# 08-Power.net
KiCad netlist of a schematic drawn in Altium Designer
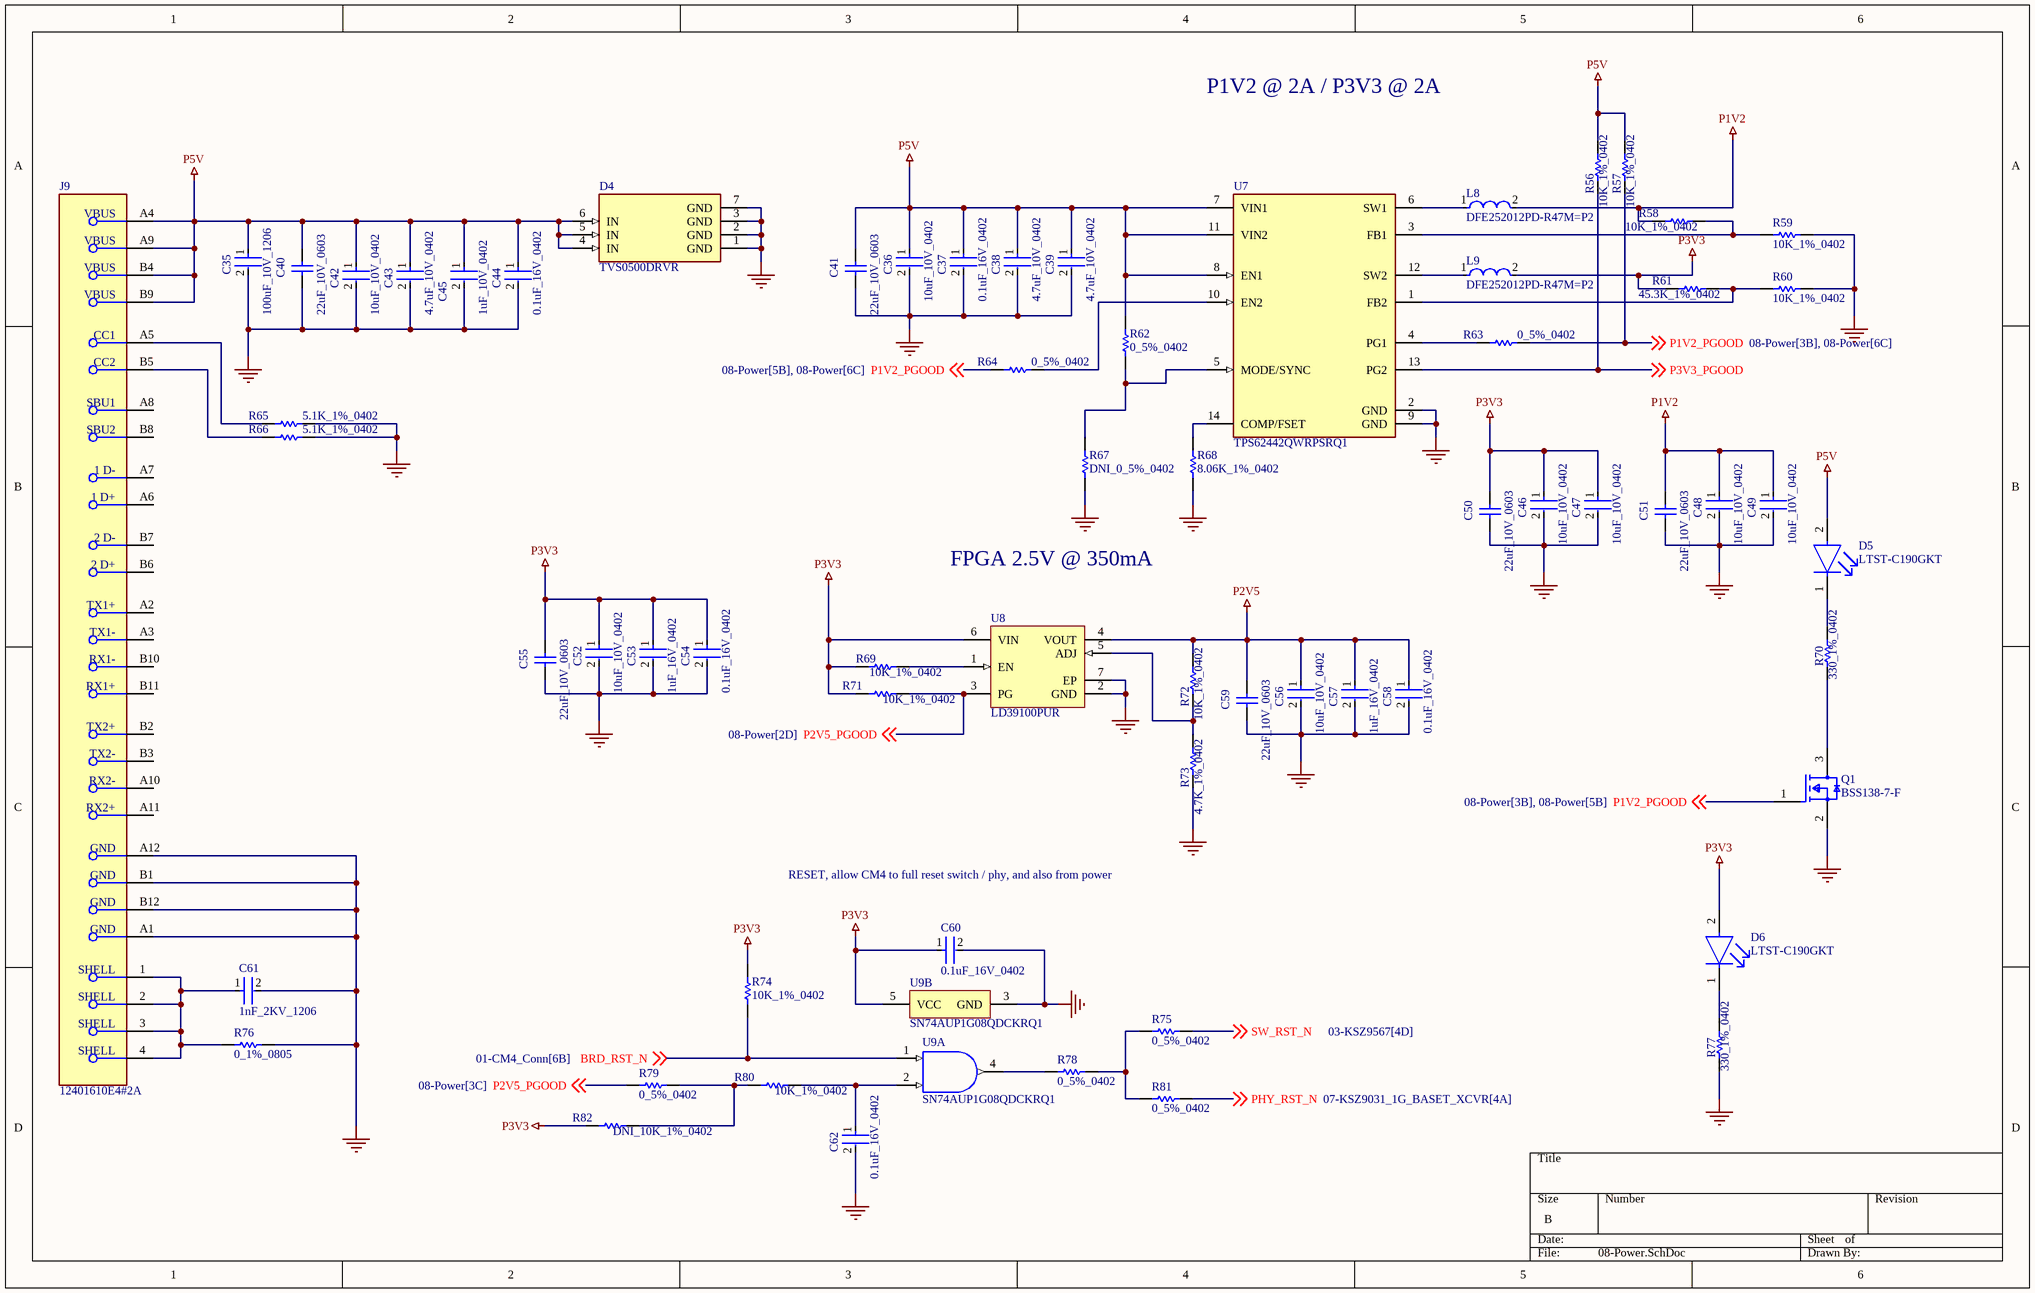
[diagram p0: 08-Power.SchDoc]

(export (version "E")
  (design (tool "Eeschema 10.0.6"))
  (components
    (comp (ref "C35")
      (value "100uF_10V_1206")
      (footprint "FP-C3216-160-0_3-IPC_C")
      (description "Multilayer Ceramic Capacitors 100uF ±20% 10V X5R SMD 1206")
      (fields (field (name "VOLTAGE") "10V") (field (name "TOLERANCE") "20%"))
      (libsource (lib "Altium Content Vault") (part "02cd4be3c70576c341d710602a673aa"))
    )
    (comp (ref "C36")
      (value "10uF_10V_0402")
      (footprint "FP-CL05A106MP5NUNC-MFG")
      (description "CAP CER 10UF 10V X5R 0402")
      (fields
        (field (name "OCTOPART") "https://octopart.com/cl05a106mp5nunc-samsung-22457395")
        (field (name "TOLERANCE") "20%")
      )
      (libsource (lib "Altium Content Vault") (part "b4654b650e69147ec39a6b967a45e02"))
    )
    (comp (ref "C37")
      (value "0.1uF_16V_0402")
      (footprint "FP-C0402-BB-MFG")
      (description "CAP CER 0.1UF 16V 5% X7R 0402")
      (fields
        (field (name "MANUFACTURER") "Kemet")
        (field (name "MANUFACTURER PART NUMBER") "C0402C104J4RACTU")
      )
      (libsource (lib "Altium Content Vault") (part "b4654b650e69147ec39a6b967a45e02"))
    )
    (comp (ref "C38")
      (value "4.7uF_10V_0402")
      (footprint "FP-C1005-050-0_15-MFG")
      (description "CAP CER 4.7UF 10V X5R 0402")
      (fields (field (name "TOLERANCE") "10%"))
      (libsource (lib "Altium Content Vault") (part "b4654b650e69147ec39a6b967a45e02"))
    )
    (comp (ref "C39")
      (value "4.7uF_10V_0402")
      (footprint "FP-C1005-050-0_15-MFG")
      (description "CAP CER 4.7UF 10V X5R 0402")
      (fields (field (name "TOLERANCE") "10%"))
      (libsource (lib "Altium Content Vault") (part "b4654b650e69147ec39a6b967a45e02"))
    )
    (comp (ref "C40")
      (value "22uF_10V_0603")
      (footprint "CAPC1608X100X20ML10")
      (description "Chip Capacitor, 22 uF, +/- 20%, 10 V, -55 to 85 degC, 0603 (1608 Metric), RoHS, Tape and Reel")
      (fields (field (name "MANUFACTURER") "TDK") (field (name "TOLERANCE") "±20%"))
      (libsource (lib "Altium Content Vault") (part "CAP-NP-2"))
    )
    (comp (ref "C41")
      (value "22uF_10V_0603")
      (footprint "CAPC1608X100X20ML10")
      (description "Chip Capacitor, 22 uF, +/- 20%, 10 V, -55 to 85 degC, 0603 (1608 Metric), RoHS, Tape and Reel")
      (fields (field (name "MANUFACTURER") "TDK") (field (name "TOLERANCE") "±20%"))
      (libsource (lib "Altium Content Vault") (part "CAP-NP-2"))
    )
    (comp (ref "C42")
      (value "10uF_10V_0402")
      (footprint "FP-CL05A106MP5NUNC-MFG")
      (description "CAP CER 10UF 10V X5R 0402")
      (fields
        (field (name "OCTOPART") "https://octopart.com/cl05a106mp5nunc-samsung-22457395")
        (field (name "TOLERANCE") "20%")
      )
      (libsource (lib "Altium Content Vault") (part "b4654b650e69147ec39a6b967a45e02"))
    )
    (comp (ref "C43")
      (value "4.7uF_10V_0402")
      (footprint "FP-C1005-050-0_15-MFG")
      (description "CAP CER 4.7UF 10V X5R 0402")
      (fields (field (name "TOLERANCE") "10%"))
      (libsource (lib "Altium Content Vault") (part "b4654b650e69147ec39a6b967a45e02"))
    )
    (comp (ref "C44")
      (value "0.1uF_16V_0402")
      (footprint "FP-C0402-BB-MFG")
      (description "CAP CER 0.1UF 16V 5% X7R 0402")
      (fields
        (field (name "MANUFACTURER") "Kemet")
        (field (name "MANUFACTURER PART NUMBER") "C0402C104J4RACTU")
      )
      (libsource (lib "Altium Content Vault") (part "b4654b650e69147ec39a6b967a45e02"))
    )
    (comp (ref "C45")
      (value "1uF_10V_0402")
      (footprint "FP-CL511-IPC_C")
      (description "Cap Ceramic 1uF 10V X5R ±10% SMD 0402 +85°C Paper T/R")
      (fields (field (name "TOLERANCE") "10%"))
      (libsource (lib "Altium Content Vault") (part "b4654b650e69147ec39a6b967a45e02"))
    )
    (comp (ref "C46")
      (value "10uF_10V_0402")
      (footprint "FP-CL05A106MP5NUNC-MFG")
      (description "CAP CER 10UF 10V X5R 0402")
      (fields
        (field (name "OCTOPART") "https://octopart.com/cl05a106mp5nunc-samsung-22457395")
        (field (name "TOLERANCE") "20%")
      )
      (libsource (lib "Altium Content Vault") (part "b4654b650e69147ec39a6b967a45e02"))
    )
    (comp (ref "C47")
      (value "10uF_10V_0402")
      (footprint "FP-CL05A106MP5NUNC-MFG")
      (description "CAP CER 10UF 10V X5R 0402")
      (fields
        (field (name "OCTOPART") "https://octopart.com/cl05a106mp5nunc-samsung-22457395")
        (field (name "TOLERANCE") "20%")
      )
      (libsource (lib "Altium Content Vault") (part "b4654b650e69147ec39a6b967a45e02"))
    )
    (comp (ref "C48")
      (value "10uF_10V_0402")
      (footprint "FP-CL05A106MP5NUNC-MFG")
      (description "CAP CER 10UF 10V X5R 0402")
      (fields
        (field (name "OCTOPART") "https://octopart.com/cl05a106mp5nunc-samsung-22457395")
        (field (name "TOLERANCE") "20%")
      )
      (libsource (lib "Altium Content Vault") (part "b4654b650e69147ec39a6b967a45e02"))
    )
    (comp (ref "C49")
      (value "10uF_10V_0402")
      (footprint "FP-CL05A106MP5NUNC-MFG")
      (description "CAP CER 10UF 10V X5R 0402")
      (fields
        (field (name "OCTOPART") "https://octopart.com/cl05a106mp5nunc-samsung-22457395")
        (field (name "TOLERANCE") "20%")
      )
      (libsource (lib "Altium Content Vault") (part "b4654b650e69147ec39a6b967a45e02"))
    )
    (comp (ref "C50")
      (value "22uF_10V_0603")
      (footprint "CAPC1608X100X20ML10")
      (description "Chip Capacitor, 22 uF, +/- 20%, 10 V, -55 to 85 degC, 0603 (1608 Metric), RoHS, Tape and Reel")
      (fields (field (name "MANUFACTURER") "TDK") (field (name "TOLERANCE") "±20%"))
      (libsource (lib "Altium Content Vault") (part "CAP-NP-2"))
    )
    (comp (ref "C51")
      (value "22uF_10V_0603")
      (footprint "CAPC1608X100X20ML10")
      (description "Chip Capacitor, 22 uF, +/- 20%, 10 V, -55 to 85 degC, 0603 (1608 Metric), RoHS, Tape and Reel")
      (fields (field (name "MANUFACTURER") "TDK") (field (name "TOLERANCE") "±20%"))
      (libsource (lib "Altium Content Vault") (part "CAP-NP-2"))
    )
    (comp (ref "C52")
      (value "10uF_10V_0402")
      (footprint "FP-CL05A106MP5NUNC-MFG")
      (description "CAP CER 10UF 10V X5R 0402")
      (fields
        (field (name "OCTOPART") "https://octopart.com/cl05a106mp5nunc-samsung-22457395")
        (field (name "TOLERANCE") "20%")
      )
      (libsource (lib "Altium Content Vault") (part "b4654b650e69147ec39a6b967a45e02"))
    )
    (comp (ref "C53")
      (value "1uF_16V_0402")
      (footprint "FP-0402-L_1_0_0_05-W_0_5-IPC_A")
      (description "None")
      (fields (field (name "TOLERANCE") "10%"))
      (libsource (lib "Altium Content Vault") (part "b4654b650e69147ec39a6b967a45e02"))
    )
    (comp (ref "C54")
      (value "0.1uF_16V_0402")
      (footprint "FP-C0402-BB-MFG")
      (description "CAP CER 0.1UF 16V 5% X7R 0402")
      (fields
        (field (name "MANUFACTURER") "Kemet")
        (field (name "MANUFACTURER PART NUMBER") "C0402C104J4RACTU")
      )
      (libsource (lib "Altium Content Vault") (part "b4654b650e69147ec39a6b967a45e02"))
    )
    (comp (ref "C55")
      (value "22uF_10V_0603")
      (footprint "CAPC1608X100X20ML10")
      (description "Chip Capacitor, 22 uF, +/- 20%, 10 V, -55 to 85 degC, 0603 (1608 Metric), RoHS, Tape and Reel")
      (fields (field (name "MANUFACTURER") "TDK") (field (name "TOLERANCE") "±20%"))
      (libsource (lib "Altium Content Vault") (part "CAP-NP-2"))
    )
    (comp (ref "C56")
      (value "10uF_10V_0402")
      (footprint "FP-CL05A106MP5NUNC-MFG")
      (description "CAP CER 10UF 10V X5R 0402")
      (fields
        (field (name "OCTOPART") "https://octopart.com/cl05a106mp5nunc-samsung-22457395")
        (field (name "TOLERANCE") "20%")
      )
      (libsource (lib "Altium Content Vault") (part "b4654b650e69147ec39a6b967a45e02"))
    )
    (comp (ref "C57")
      (value "1uF_16V_0402")
      (footprint "FP-0402-L_1_0_0_05-W_0_5-IPC_A")
      (description "None")
      (fields (field (name "TOLERANCE") "10%"))
      (libsource (lib "Altium Content Vault") (part "b4654b650e69147ec39a6b967a45e02"))
    )
    (comp (ref "C58")
      (value "0.1uF_16V_0402")
      (footprint "FP-C0402-BB-MFG")
      (description "CAP CER 0.1UF 16V 5% X7R 0402")
      (fields
        (field (name "MANUFACTURER") "Kemet")
        (field (name "MANUFACTURER PART NUMBER") "C0402C104J4RACTU")
      )
      (libsource (lib "Altium Content Vault") (part "b4654b650e69147ec39a6b967a45e02"))
    )
    (comp (ref "C59")
      (value "22uF_10V_0603")
      (footprint "CAPC1608X100X20ML10")
      (description "Chip Capacitor, 22 uF, +/- 20%, 10 V, -55 to 85 degC, 0603 (1608 Metric), RoHS, Tape and Reel")
      (fields (field (name "MANUFACTURER") "TDK") (field (name "TOLERANCE") "±20%"))
      (libsource (lib "Altium Content Vault") (part "CAP-NP-2"))
    )
    (comp (ref "C60")
      (value "0.1uF_16V_0402")
      (footprint "FP-C0402-BB-MFG")
      (description "CAP CER 0.1UF 16V 5% X7R 0402")
      (fields
        (field (name "MANUFACTURER") "Kemet")
        (field (name "MANUFACTURER PART NUMBER") "C0402C104J4RACTU")
      )
      (libsource (lib "Altium Content Vault") (part "b4654b650e69147ec39a6b967a45e02"))
    )
    (comp (ref "C61")
      (value "1nF_2KV_1206")
      (footprint "FP-CC1206-0_3-1_45-IPC_C")
      (description "CAP CER 1000PF 2KV X7R 1206")
      (fields (field (name "TOLERANCE") "10%") (field (name "VOLTAGE") "2kV"))
      (libsource (lib "Altium Content Vault") (part "02cd4be3c70576c341d710602a673aa"))
    )
    (comp (ref "C62")
      (value "0.1uF_16V_0402")
      (footprint "FP-C0402-BB-MFG")
      (description "CAP CER 0.1UF 16V 5% X7R 0402")
      (fields
        (field (name "MANUFACTURER") "Kemet")
        (field (name "MANUFACTURER PART NUMBER") "C0402C104J4RACTU")
      )
      (libsource (lib "Altium Content Vault") (part "b4654b650e69147ec39a6b967a45e02"))
    )
    (comp (ref "D4")
      (value "TVS0500DRVR")
      (footprint "FP-DRV0006A-MFG")
      (description "UNIDIR PRECISION SURGE DIODE")
      (libsource (lib "Altium Content Vault") (part "41370df9eefb4491f57eee86c9ac516"))
    )
    (comp (ref "D5")
      (value "LTST-C190GKT")
      (footprint "FP-LTST-C190GKT-MFG")
      (description "LED GREEN CLEAR CHIP SMD")
      (fields (field (name "VOLTAGE") "2V"))
      (libsource (lib "Altium Content Vault") (part "8706943c75ba83719d021d2fdc84c58"))
    )
    (comp (ref "D6")
      (value "LTST-C190GKT")
      (footprint "FP-LTST-C190GKT-MFG")
      (description "LED GREEN CLEAR CHIP SMD")
      (fields (field (name "VOLTAGE") "2V"))
      (libsource (lib "Altium Content Vault") (part "8706943c75ba83719d021d2fdc84c58"))
    )
    (comp (ref "J9")
      (value "12401610E4#2A")
      (footprint "FP-12401610E4#2A-MFG")
      (description "CONN RCP USB3.1 TYPEC 24P SMD RA")
      (libsource (lib "Altium Content Vault") (part "7c76f4c47d7e2af8b8797da79635f2a"))
    )
    (comp (ref "L8")
      (value "DFE252012PD-R47M=P2")
      (footprint "FP-DFE252012C-IPC_A")
      (description "Shielded Wirewound Inductor 0.47uH 20% 4000mA 0.027Ω 1008 (2520)")
      (libsource (lib "Altium Content Vault") (part "725321dda6339637d4d059423bc1c3c"))
    )
    (comp (ref "L9")
      (value "DFE252012PD-R47M=P2")
      (footprint "FP-DFE252012C-IPC_A")
      (description "Shielded Wirewound Inductor 0.47uH 20% 4000mA 0.027Ω 1008 (2520)")
      (libsource (lib "Altium Content Vault") (part "725321dda6339637d4d059423bc1c3c"))
    )
    (comp (ref "Q1")
      (value "BSS138-7-F")
      (footprint "FP-SOT23_Standard-MFG")
      (fields (field (name "VOLTAGE") "50V"))
      (libsource (lib "Altium Content Vault") (part "0a9ea7c96deaaede766a5b531c28de0"))
    )
    (comp (ref "R56")
      (value "10K_1%_0402")
      (footprint "RESC1005X40X25NL10T10")
      (fields (field (name "MANUFACTURER") "Bourns") (field (name "PART NUMBER") "CR0402-FX-1002GLF"))
      (libsource (lib "Altium Content Vault") (part "RES"))
    )
    (comp (ref "R57")
      (value "10K_1%_0402")
      (footprint "RESC1005X40X25NL10T10")
      (fields (field (name "MANUFACTURER") "Bourns") (field (name "PART NUMBER") "CR0402-FX-1002GLF"))
      (libsource (lib "Altium Content Vault") (part "RES"))
    )
    (comp (ref "R58")
      (value "10K_1%_0402")
      (footprint "RESC1005X40X25NL10T10")
      (fields (field (name "MANUFACTURER") "Bourns") (field (name "PART NUMBER") "CR0402-FX-1002GLF"))
      (libsource (lib "Altium Content Vault") (part "RES"))
    )
    (comp (ref "R59")
      (value "10K_1%_0402")
      (footprint "RESC1005X40X25NL10T10")
      (fields (field (name "MANUFACTURER") "Bourns") (field (name "PART NUMBER") "CR0402-FX-1002GLF"))
      (libsource (lib "Altium Content Vault") (part "RES"))
    )
    (comp (ref "R60")
      (value "10K_1%_0402")
      (footprint "RESC1005X40X25NL10T10")
      (fields (field (name "MANUFACTURER") "Bourns") (field (name "PART NUMBER") "CR0402-FX-1002GLF"))
      (libsource (lib "Altium Content Vault") (part "RES"))
    )
    (comp (ref "R61")
      (value "45.3K_1%_0402")
      (footprint "RESC0402(1005)_L")
      (description "45K3 0.063W 1% 0402 (1005 Metric)  SMD")
      (fields (field (name "TOLERANCE") "1 %") (field (name "POWER") "0.063 W"))
      (libsource (lib "Altium Content Vault") (part "RES"))
    )
    (comp (ref "R62")
      (value "0_5%_0402")
      (footprint "RESC1005X40X25NL05T10")
      (fields (field (name "MANUFACTURER") "Panasonic") (field (name "PART NUMBER") "ERJ-U020R00X"))
      (libsource (lib "Altium Content Vault") (part "RES"))
    )
    (comp (ref "R63")
      (value "0_5%_0402")
      (footprint "RESC1005X40X25NL05T10")
      (fields (field (name "MANUFACTURER") "Panasonic") (field (name "PART NUMBER") "ERJ-U020R00X"))
      (libsource (lib "Altium Content Vault") (part "RES"))
    )
    (comp (ref "R64")
      (value "0_5%_0402")
      (footprint "RESC1005X40X25NL05T10")
      (fields (field (name "MANUFACTURER") "Panasonic") (field (name "PART NUMBER") "ERJ-U020R00X"))
      (libsource (lib "Altium Content Vault") (part "RES"))
    )
    (comp (ref "R65")
      (value "5.1K_1%_0402")
      (footprint "RESC1005X40X25NL05T10")
      (fields (field (name "PART NUMBER") "RC0402FR-075K1L") (field (name "MANUFACTURER") "Yageo / Phycomp"))
      (libsource (lib "Altium Content Vault") (part "RES"))
    )
    (comp (ref "R66")
      (value "5.1K_1%_0402")
      (footprint "RESC1005X40X25NL05T10")
      (fields (field (name "PART NUMBER") "RC0402FR-075K1L") (field (name "MANUFACTURER") "Yageo / Phycomp"))
      (libsource (lib "Altium Content Vault") (part "RES"))
    )
    (comp (ref "R67")
      (value "DNI_0_5%_0402")
      (footprint "RESC1005X40X25NL05T10")
      (fields (field (name "MANUFACTURER") "Panasonic") (field (name "PART NUMBER") "ERJ-U020R00X"))
      (libsource (lib "Altium Content Vault") (part "RES"))
    )
    (comp (ref "R68")
      (value "8.06K_1%_0402")
      (footprint "RESC1005X40X25ML05T05")
      (description "Chip Resistor, 8.06 KOhm, +/- 1%, 63 mW, -55 to 155 degC, 0402 (1005 Metric), RoHS, Tape and Reel")
      (fields (field (name "PARTNUMBER") "CRCW04028K06FKED") (field (name "TOLERANCE") "1%"))
      (libsource (lib "Altium Content Vault") (part "RES-2"))
    )
    (comp (ref "R69")
      (value "10K_1%_0402")
      (footprint "RESC1005X40X25NL10T10")
      (fields (field (name "MANUFACTURER") "Bourns") (field (name "PART NUMBER") "CR0402-FX-1002GLF"))
      (libsource (lib "Altium Content Vault") (part "RES"))
    )
    (comp (ref "R70")
      (value "330_1%_0402")
      (footprint "RESC1005X40X25NL10T10")
      (fields (field (name "MANUFACTURER") "Panasonic") (field (name "PART NUMBER") "ERA-2AED331X"))
      (libsource (lib "Altium Content Vault") (part "RES"))
    )
    (comp (ref "R71")
      (value "10K_1%_0402")
      (footprint "RESC1005X40X25NL10T10")
      (fields (field (name "MANUFACTURER") "Bourns") (field (name "PART NUMBER") "CR0402-FX-1002GLF"))
      (libsource (lib "Altium Content Vault") (part "RES"))
    )
    (comp (ref "R72")
      (value "10K_1%_0402")
      (footprint "RESC1005X40X25NL10T10")
      (fields (field (name "MANUFACTURER") "Bourns") (field (name "PART NUMBER") "CR0402-FX-1002GLF"))
      (libsource (lib "Altium Content Vault") (part "RES"))
    )
    (comp (ref "R73")
      (value "4.7K_1%_0402")
      (footprint "RESC1005X40X25NL10T10")
      (fields (field (name "MANUFACTURER") "Bourns") (field (name "PART NUMBER") "CR0402-FX-4701GLF"))
      (libsource (lib "Altium Content Vault") (part "RES"))
    )
    (comp (ref "R74")
      (value "10K_1%_0402")
      (footprint "RESC1005X40X25NL10T10")
      (fields (field (name "MANUFACTURER") "Bourns") (field (name "PART NUMBER") "CR0402-FX-1002GLF"))
      (libsource (lib "Altium Content Vault") (part "RES"))
    )
    (comp (ref "R75")
      (value "0_5%_0402")
      (footprint "RESC1005X40X25NL05T10")
      (fields (field (name "MANUFACTURER") "Panasonic") (field (name "PART NUMBER") "ERJ-U020R00X"))
      (libsource (lib "Altium Content Vault") (part "RES"))
    )
    (comp (ref "R76")
      (value "0_1%_0805")
      (footprint "RESC2013X60X35NL10T20")
      (fields (field (name "MANUFACTURER") "Yageo") (field (name "PART NUMBER") "AC0805FR-070RL"))
      (libsource (lib "Altium Content Vault") (part "RES"))
    )
    (comp (ref "R77")
      (value "330_1%_0402")
      (footprint "RESC1005X40X25NL10T10")
      (fields (field (name "MANUFACTURER") "Panasonic") (field (name "PART NUMBER") "ERA-2AED331X"))
      (libsource (lib "Altium Content Vault") (part "RES"))
    )
    (comp (ref "R78")
      (value "0_5%_0402")
      (footprint "RESC1005X40X25NL05T10")
      (fields (field (name "MANUFACTURER") "Panasonic") (field (name "PART NUMBER") "ERJ-U020R00X"))
      (libsource (lib "Altium Content Vault") (part "RES"))
    )
    (comp (ref "R79")
      (value "0_5%_0402")
      (footprint "RESC1005X40X25NL05T10")
      (fields (field (name "MANUFACTURER") "Panasonic") (field (name "PART NUMBER") "ERJ-U020R00X"))
      (libsource (lib "Altium Content Vault") (part "RES"))
    )
    (comp (ref "R80")
      (value "10K_1%_0402")
      (footprint "RESC1005X40X25NL10T10")
      (fields (field (name "MANUFACTURER") "Bourns") (field (name "PART NUMBER") "CR0402-FX-1002GLF"))
      (libsource (lib "Altium Content Vault") (part "RES"))
    )
    (comp (ref "R81")
      (value "0_5%_0402")
      (footprint "RESC1005X40X25NL05T10")
      (fields (field (name "MANUFACTURER") "Panasonic") (field (name "PART NUMBER") "ERJ-U020R00X"))
      (libsource (lib "Altium Content Vault") (part "RES"))
    )
    (comp (ref "R82")
      (value "DNI_10K_1%_0402")
      (footprint "RESC1005X40X25NL10T10")
      (fields (field (name "MANUFACTURER") "Bourns") (field (name "PART NUMBER") "CR0402-FX-1002GLF"))
      (libsource (lib "Altium Content Vault") (part "RES"))
    )
    (comp (ref "U7")
      (value "TPS62442QWRPSRQ1")
      (footprint "FP-RQR0014A-MFG")
      (description "Adjustable-Frequency Dual Step-Down Converter, 2.7-6V VIN, 0.6-5.5V 2A VOUT, VQFN-HR14")
      (libsource (lib "Altium Content Vault") (part "72c5b9bb22caeb688b1070b758806aa"))
    )
    (comp (ref "U8")
      (value "LD39100PUR")
      (footprint "DFN6D_M")
      (libsource (lib "Altium Content Vault") (part "PM-REG-LD39050-SQ7A"))
    )
    (comp (ref "U9")
      (value "SN74AUP1G08QDCKRQ1")
      (footprint "DCK0005A_L")
      (description "Automotive Catalog Low-Power Single 2-Input Positive-AND Gate, DCK0005A, LARGE T&R")
      (fields
        (field (name "MANUFACTURER") "Texas Instruments")
        (field (name "GENERIC PART NUMBER") "SN74AUP1G08-Q1")
      )
      (libsource (lib "Altium Content Vault") (part "TI-SN74XXX1X08-5"))
    )
  )
  (nets
    (net (code "1") (name "BRD_RST_N") (class "Default")
      (node (ref "R74") (pin "2") (pinfunction "2_2") (pintype "passive"))
      (node (ref "U9") (pin "1") (pinfunction "A_1") (pintype "input"))
    )
    (net (code "2") (name "GND") (class "Default")
      (node (ref "C35") (pin "2") (pinfunction "2_2") (pintype "passive"))
      (node (ref "C36") (pin "2") (pinfunction "2_2") (pintype "passive"))
      (node (ref "C37") (pin "2") (pinfunction "2_2") (pintype "passive"))
      (node (ref "C38") (pin "2") (pinfunction "2_2") (pintype "passive"))
      (node (ref "C39") (pin "2") (pinfunction "2_2") (pintype "passive"))
      (node (ref "C40") (pin "1") (pinfunction "1_1") (pintype "passive"))
      (node (ref "C41") (pin "1") (pinfunction "1_1") (pintype "passive"))
      (node (ref "C42") (pin "2") (pinfunction "2_2") (pintype "passive"))
      (node (ref "C43") (pin "2") (pinfunction "2_2") (pintype "passive"))
      (node (ref "C44") (pin "2") (pinfunction "2_2") (pintype "passive"))
      (node (ref "C45") (pin "2") (pinfunction "2_2") (pintype "passive"))
      (node (ref "C46") (pin "2") (pinfunction "2_2") (pintype "passive"))
      (node (ref "C47") (pin "2") (pinfunction "2_2") (pintype "passive"))
      (node (ref "C48") (pin "2") (pinfunction "2_2") (pintype "passive"))
      (node (ref "C49") (pin "2") (pinfunction "2_2") (pintype "passive"))
      (node (ref "C50") (pin "1") (pinfunction "1_1") (pintype "passive"))
      (node (ref "C51") (pin "1") (pinfunction "1_1") (pintype "passive"))
      (node (ref "C52") (pin "2") (pinfunction "2_2") (pintype "passive"))
      (node (ref "C53") (pin "2") (pinfunction "2_2") (pintype "passive"))
      (node (ref "C54") (pin "2") (pinfunction "2_2") (pintype "passive"))
      (node (ref "C55") (pin "1") (pinfunction "1_1") (pintype "passive"))
      (node (ref "C56") (pin "2") (pinfunction "2_2") (pintype "passive"))
      (node (ref "C57") (pin "2") (pinfunction "2_2") (pintype "passive"))
      (node (ref "C58") (pin "2") (pinfunction "2_2") (pintype "passive"))
      (node (ref "C59") (pin "1") (pinfunction "1_1") (pintype "passive"))
      (node (ref "C60") (pin "2") (pinfunction "2_2") (pintype "passive"))
      (node (ref "C61") (pin "2") (pinfunction "2_2") (pintype "passive"))
      (node (ref "C62") (pin "2") (pinfunction "2_2") (pintype "passive"))
      (node (ref "D4") (pin "1") (pinfunction "GND_1") (pintype "power_in"))
      (node (ref "D4") (pin "2") (pinfunction "GND_2") (pintype "power_in"))
      (node (ref "D4") (pin "3") (pinfunction "GND_3") (pintype "power_in"))
      (node (ref "D4") (pin "7") (pinfunction "GND_7") (pintype "power_in"))
      (node (ref "J9") (pin "A1") (pinfunction "GND_A1") (pintype "power_in"))
      (node (ref "J9") (pin "A12") (pinfunction "GND_A12") (pintype "power_in"))
      (node (ref "J9") (pin "B1") (pinfunction "GND_B1") (pintype "power_in"))
      (node (ref "J9") (pin "B12") (pinfunction "GND_B12") (pintype "power_in"))
      (node (ref "Q1") (pin "2") (pinfunction "S_2") (pintype "passive"))
      (node (ref "R59") (pin "1") (pinfunction "1_1") (pintype "passive"))
      (node (ref "R60") (pin "1") (pinfunction "1_1") (pintype "passive"))
      (node (ref "R65") (pin "2") (pinfunction "2_2") (pintype "passive"))
      (node (ref "R66") (pin "2") (pinfunction "2_2") (pintype "passive"))
      (node (ref "R67") (pin "1") (pinfunction "1_1") (pintype "passive"))
      (node (ref "R68") (pin "1") (pinfunction "1_1") (pintype "passive"))
      (node (ref "R73") (pin "1") (pinfunction "1_1") (pintype "passive"))
      (node (ref "R76") (pin "2") (pinfunction "2_2") (pintype "passive"))
      (node (ref "R77") (pin "1") (pinfunction "1_1") (pintype "passive"))
      (node (ref "U7") (pin "2") (pinfunction "GND_2") (pintype "power_in"))
      (node (ref "U7") (pin "9") (pinfunction "GND_9") (pintype "power_in"))
      (node (ref "U8") (pin "2") (pinfunction "GND_2") (pintype "power_in"))
      (node (ref "U8") (pin "7") (pinfunction "EP_7") (pintype "power_in"))
      (node (ref "U9") (pin "3") (pinfunction "GND_3") (pintype "power_in"))
    )
    (net (code "3") (name "Net-(C61-Pad1)") (class "Default")
      (node (ref "C61") (pin "1") (pinfunction "1_1") (pintype "passive"))
      (node (ref "J9") (pin "1") (pinfunction "SHELL_1") (pintype "power_in"))
      (node (ref "J9") (pin "2") (pinfunction "SHELL_2") (pintype "power_in"))
      (node (ref "J9") (pin "3") (pinfunction "SHELL_3") (pintype "power_in"))
      (node (ref "J9") (pin "4") (pinfunction "SHELL_4") (pintype "power_in"))
      (node (ref "R76") (pin "1") (pinfunction "1_1") (pintype "passive"))
    )
    (net (code "4") (name "Net-(D5-C)") (class "Default")
      (node (ref "D5") (pin "1") (pinfunction "C_1") (pintype "passive"))
      (node (ref "R70") (pin "2") (pinfunction "2_2") (pintype "passive"))
    )
    (net (code "5") (name "Net-(D6-C)") (class "Default")
      (node (ref "D6") (pin "1") (pinfunction "C_1") (pintype "passive"))
      (node (ref "R77") (pin "2") (pinfunction "2_2") (pintype "passive"))
    )
    (net (code "6") (name "Net-(J9-CC1)") (class "Default")
      (node (ref "J9") (pin "A5") (pinfunction "CC1_A5") (pintype "passive"))
      (node (ref "R65") (pin "1") (pinfunction "1_1") (pintype "passive"))
    )
    (net (code "7") (name "Net-(J9-CC2)") (class "Default")
      (node (ref "J9") (pin "B5") (pinfunction "CC2_B5") (pintype "passive"))
      (node (ref "R66") (pin "1") (pinfunction "1_1") (pintype "passive"))
    )
    (net (code "8") (name "Net-(Q1-D)") (class "Default")
      (node (ref "Q1") (pin "3") (pinfunction "D_3") (pintype "passive"))
      (node (ref "R70") (pin "1") (pinfunction "1_1") (pintype "passive"))
    )
    (net (code "9") (name "Net-(R75-Pad2)") (class "Default")
      (node (ref "R75") (pin "2") (pinfunction "2_2") (pintype "passive"))
      (node (ref "R78") (pin "1") (pinfunction "1_1") (pintype "passive"))
      (node (ref "R81") (pin "2") (pinfunction "2_2") (pintype "passive"))
    )
    (net (code "10") (name "Net-(R79-Pad1)") (class "Default")
      (node (ref "R79") (pin "1") (pinfunction "1_1") (pintype "passive"))
      (node (ref "R80") (pin "2") (pinfunction "2_2") (pintype "passive"))
      (node (ref "R82") (pin "1") (pinfunction "1_1") (pintype "passive"))
    )
    (net (code "11") (name "Net-(U7-COMP{slash}FSET)") (class "Default")
      (node (ref "R68") (pin "2") (pinfunction "2_2") (pintype "passive"))
      (node (ref "U7") (pin "14") (pinfunction "COMP/FSET_14") (pintype "passive"))
    )
    (net (code "12") (name "Net-(U7-EN2)") (class "Default")
      (node (ref "R64") (pin "2") (pinfunction "2_2") (pintype "passive"))
      (node (ref "U7") (pin "10") (pinfunction "EN2_10") (pintype "input"))
    )
    (net (code "13") (name "Net-(U7-FB1)") (class "Default")
      (node (ref "R58") (pin "1") (pinfunction "1_1") (pintype "passive"))
      (node (ref "R59") (pin "2") (pinfunction "2_2") (pintype "passive"))
      (node (ref "U7") (pin "3") (pinfunction "FB1_3") (pintype "passive"))
    )
    (net (code "14") (name "Net-(U7-FB2)") (class "Default")
      (node (ref "R60") (pin "2") (pinfunction "2_2") (pintype "passive"))
      (node (ref "R61") (pin "2") (pinfunction "2_2") (pintype "passive"))
      (node (ref "U7") (pin "1") (pinfunction "FB2_1") (pintype "passive"))
    )
    (net (code "15") (name "Net-(U7-MODE{slash}SYNC)") (class "Default")
      (node (ref "R62") (pin "1") (pinfunction "1_1") (pintype "passive"))
      (node (ref "R67") (pin "2") (pinfunction "2_2") (pintype "passive"))
      (node (ref "U7") (pin "5") (pinfunction "MODE/SYNC_5") (pintype "input"))
    )
    (net (code "16") (name "Net-(U7-PG1)") (class "Default")
      (node (ref "R63") (pin "1") (pinfunction "1_1") (pintype "passive"))
      (node (ref "U7") (pin "4") (pinfunction "PG1_4") (pintype "open_collector"))
    )
    (net (code "17") (name "Net-(U7-SW1)") (class "Default")
      (node (ref "L8") (pin "1") (pinfunction "1_1") (pintype "passive"))
      (node (ref "U7") (pin "6") (pinfunction "SW1_6") (pintype "passive"))
    )
    (net (code "18") (name "Net-(U7-SW2)") (class "Default")
      (node (ref "L9") (pin "1") (pinfunction "1_1") (pintype "passive"))
      (node (ref "U7") (pin "12") (pinfunction "SW2_12") (pintype "passive"))
    )
    (net (code "19") (name "Net-(U8-ADJ)") (class "Default")
      (node (ref "R72") (pin "1") (pinfunction "1_1") (pintype "passive"))
      (node (ref "R73") (pin "2") (pinfunction "2_2") (pintype "passive"))
      (node (ref "U8") (pin "5") (pinfunction "ADJ_5") (pintype "input"))
    )
    (net (code "20") (name "Net-(U8-EN)") (class "Default")
      (node (ref "R69") (pin "1") (pinfunction "1_1") (pintype "passive"))
      (node (ref "U8") (pin "1") (pinfunction "EN_1") (pintype "input"))
    )
    (net (code "21") (name "Net-(U9A-B)") (class "Default")
      (node (ref "C62") (pin "1") (pinfunction "1_1") (pintype "passive"))
      (node (ref "R80") (pin "1") (pinfunction "1_1") (pintype "passive"))
      (node (ref "U9") (pin "2") (pinfunction "B_2") (pintype "input"))
    )
    (net (code "22") (name "Net-(U9A-Y)") (class "Default")
      (node (ref "R78") (pin "2") (pinfunction "2_2") (pintype "passive"))
      (node (ref "U9") (pin "4") (pinfunction "Y_4") (pintype "output"))
    )
    (net (code "23") (name "P1V2") (class "Default")
      (node (ref "C48") (pin "1") (pinfunction "1_1") (pintype "passive"))
      (node (ref "C49") (pin "1") (pinfunction "1_1") (pintype "passive"))
      (node (ref "C51") (pin "2") (pinfunction "2_2") (pintype "passive"))
      (node (ref "L8") (pin "2") (pinfunction "2_2") (pintype "passive"))
      (node (ref "R58") (pin "2") (pinfunction "2_2") (pintype "passive"))
    )
    (net (code "24") (name "P1V2_PGOOD") (class "Default")
      (node (ref "Q1") (pin "1") (pinfunction "G_1") (pintype "passive"))
      (node (ref "R57") (pin "1") (pinfunction "1_1") (pintype "passive"))
      (node (ref "R63") (pin "2") (pinfunction "2_2") (pintype "passive"))
      (node (ref "R64") (pin "1") (pinfunction "1_1") (pintype "passive"))
    )
    (net (code "25") (name "P2V5") (class "Default")
      (node (ref "C56") (pin "1") (pinfunction "1_1") (pintype "passive"))
      (node (ref "C57") (pin "1") (pinfunction "1_1") (pintype "passive"))
      (node (ref "C58") (pin "1") (pinfunction "1_1") (pintype "passive"))
      (node (ref "C59") (pin "2") (pinfunction "2_2") (pintype "passive"))
      (node (ref "R72") (pin "2") (pinfunction "2_2") (pintype "passive"))
      (node (ref "U8") (pin "4") (pinfunction "VOUT_4") (pintype "power_in"))
    )
    (net (code "26") (name "P2V5_PGOOD") (class "Default")
      (node (ref "R71") (pin "1") (pinfunction "1_1") (pintype "passive"))
      (node (ref "R79") (pin "2") (pinfunction "2_2") (pintype "passive"))
      (node (ref "U8") (pin "3") (pinfunction "PG_3") (pintype "open_collector"))
    )
    (net (code "27") (name "P3V3") (class "Default")
      (node (ref "C46") (pin "1") (pinfunction "1_1") (pintype "passive"))
      (node (ref "C47") (pin "1") (pinfunction "1_1") (pintype "passive"))
      (node (ref "C50") (pin "2") (pinfunction "2_2") (pintype "passive"))
      (node (ref "C52") (pin "1") (pinfunction "1_1") (pintype "passive"))
      (node (ref "C53") (pin "1") (pinfunction "1_1") (pintype "passive"))
      (node (ref "C54") (pin "1") (pinfunction "1_1") (pintype "passive"))
      (node (ref "C55") (pin "2") (pinfunction "2_2") (pintype "passive"))
      (node (ref "C60") (pin "1") (pinfunction "1_1") (pintype "passive"))
      (node (ref "D6") (pin "2") (pinfunction "A_2") (pintype "passive"))
      (node (ref "L9") (pin "2") (pinfunction "2_2") (pintype "passive"))
      (node (ref "R61") (pin "1") (pinfunction "1_1") (pintype "passive"))
      (node (ref "R69") (pin "2") (pinfunction "2_2") (pintype "passive"))
      (node (ref "R71") (pin "2") (pinfunction "2_2") (pintype "passive"))
      (node (ref "R74") (pin "1") (pinfunction "1_1") (pintype "passive"))
      (node (ref "R82") (pin "2") (pinfunction "2_2") (pintype "passive"))
      (node (ref "U8") (pin "6") (pinfunction "VIN_6") (pintype "power_in"))
      (node (ref "U9") (pin "5") (pinfunction "VCC_5") (pintype "power_in"))
    )
    (net (code "28") (name "P3V3_PGOOD") (class "Default")
      (node (ref "R56") (pin "1") (pinfunction "1_1") (pintype "passive"))
      (node (ref "U7") (pin "13") (pinfunction "PG2_13") (pintype "open_collector"))
    )
    (net (code "29") (name "P5V") (class "Default")
      (node (ref "C35") (pin "1") (pinfunction "1_1") (pintype "passive"))
      (node (ref "C36") (pin "1") (pinfunction "1_1") (pintype "passive"))
      (node (ref "C37") (pin "1") (pinfunction "1_1") (pintype "passive"))
      (node (ref "C38") (pin "1") (pinfunction "1_1") (pintype "passive"))
      (node (ref "C39") (pin "1") (pinfunction "1_1") (pintype "passive"))
      (node (ref "C40") (pin "2") (pinfunction "2_2") (pintype "passive"))
      (node (ref "C41") (pin "2") (pinfunction "2_2") (pintype "passive"))
      (node (ref "C42") (pin "1") (pinfunction "1_1") (pintype "passive"))
      (node (ref "C43") (pin "1") (pinfunction "1_1") (pintype "passive"))
      (node (ref "C44") (pin "1") (pinfunction "1_1") (pintype "passive"))
      (node (ref "C45") (pin "1") (pinfunction "1_1") (pintype "passive"))
      (node (ref "D4") (pin "4") (pinfunction "IN_4") (pintype "input"))
      (node (ref "D4") (pin "5") (pinfunction "IN_5") (pintype "input"))
      (node (ref "D4") (pin "6") (pinfunction "IN_6") (pintype "input"))
      (node (ref "D5") (pin "2") (pinfunction "A_2") (pintype "passive"))
      (node (ref "J9") (pin "A4") (pinfunction "VBUS_A4") (pintype "power_in"))
      (node (ref "J9") (pin "A9") (pinfunction "VBUS_A9") (pintype "power_in"))
      (node (ref "J9") (pin "B4") (pinfunction "VBUS_B4") (pintype "power_in"))
      (node (ref "J9") (pin "B9") (pinfunction "VBUS_B9") (pintype "power_in"))
      (node (ref "R56") (pin "2") (pinfunction "2_2") (pintype "passive"))
      (node (ref "R57") (pin "2") (pinfunction "2_2") (pintype "passive"))
      (node (ref "R62") (pin "2") (pinfunction "2_2") (pintype "passive"))
      (node (ref "U7") (pin "11") (pinfunction "VIN2_11") (pintype "power_in"))
      (node (ref "U7") (pin "7") (pinfunction "VIN1_7") (pintype "power_in"))
      (node (ref "U7") (pin "8") (pinfunction "EN1_8") (pintype "input"))
    )
    (net (code "30") (name "PHY_RST_N") (class "Default")
      (node (ref "R81") (pin "1") (pinfunction "1_1") (pintype "passive"))
    )
    (net (code "31") (name "SW_RST_N") (class "Default")
      (node (ref "R75") (pin "1") (pinfunction "1_1") (pintype "passive"))
    )
    (net (code "32") (name "unconnected-(J9-1_D+-PadA6)") (class "Default")
      (node (ref "J9") (pin "A6") (pinfunction "1_D+_A6") (pintype "passive"))
    )
    (net (code "33") (name "unconnected-(J9-1_D--PadA7)") (class "Default")
      (node (ref "J9") (pin "A7") (pinfunction "1_D-_A7") (pintype "passive"))
    )
    (net (code "34") (name "unconnected-(J9-2_D+-PadB6)") (class "Default")
      (node (ref "J9") (pin "B6") (pinfunction "2_D+_B6") (pintype "passive"))
    )
    (net (code "35") (name "unconnected-(J9-2_D--PadB7)") (class "Default")
      (node (ref "J9") (pin "B7") (pinfunction "2_D-_B7") (pintype "passive"))
    )
    (net (code "36") (name "unconnected-(J9-RX1+-PadB11)") (class "Default")
      (node (ref "J9") (pin "B11") (pinfunction "RX1+_B11") (pintype "passive"))
    )
    (net (code "37") (name "unconnected-(J9-RX1--PadB10)") (class "Default")
      (node (ref "J9") (pin "B10") (pinfunction "RX1-_B10") (pintype "passive"))
    )
    (net (code "38") (name "unconnected-(J9-RX2+-PadA11)") (class "Default")
      (node (ref "J9") (pin "A11") (pinfunction "RX2+_A11") (pintype "passive"))
    )
    (net (code "39") (name "unconnected-(J9-RX2--PadA10)") (class "Default")
      (node (ref "J9") (pin "A10") (pinfunction "RX2-_A10") (pintype "passive"))
    )
    (net (code "40") (name "unconnected-(J9-SBU1-PadA8)") (class "Default")
      (node (ref "J9") (pin "A8") (pinfunction "SBU1_A8") (pintype "passive"))
    )
    (net (code "41") (name "unconnected-(J9-SBU2-PadB8)") (class "Default")
      (node (ref "J9") (pin "B8") (pinfunction "SBU2_B8") (pintype "passive"))
    )
    (net (code "42") (name "unconnected-(J9-TX1+-PadA2)") (class "Default")
      (node (ref "J9") (pin "A2") (pinfunction "TX1+_A2") (pintype "passive"))
    )
    (net (code "43") (name "unconnected-(J9-TX1--PadA3)") (class "Default")
      (node (ref "J9") (pin "A3") (pinfunction "TX1-_A3") (pintype "passive"))
    )
    (net (code "44") (name "unconnected-(J9-TX2+-PadB2)") (class "Default")
      (node (ref "J9") (pin "B2") (pinfunction "TX2+_B2") (pintype "passive"))
    )
    (net (code "45") (name "unconnected-(J9-TX2--PadB3)") (class "Default")
      (node (ref "J9") (pin "B3") (pinfunction "TX2-_B3") (pintype "passive"))
    )
  )
)
